# Powersupply.net
KiCad netlist of a schematic drawn in Altium Designer
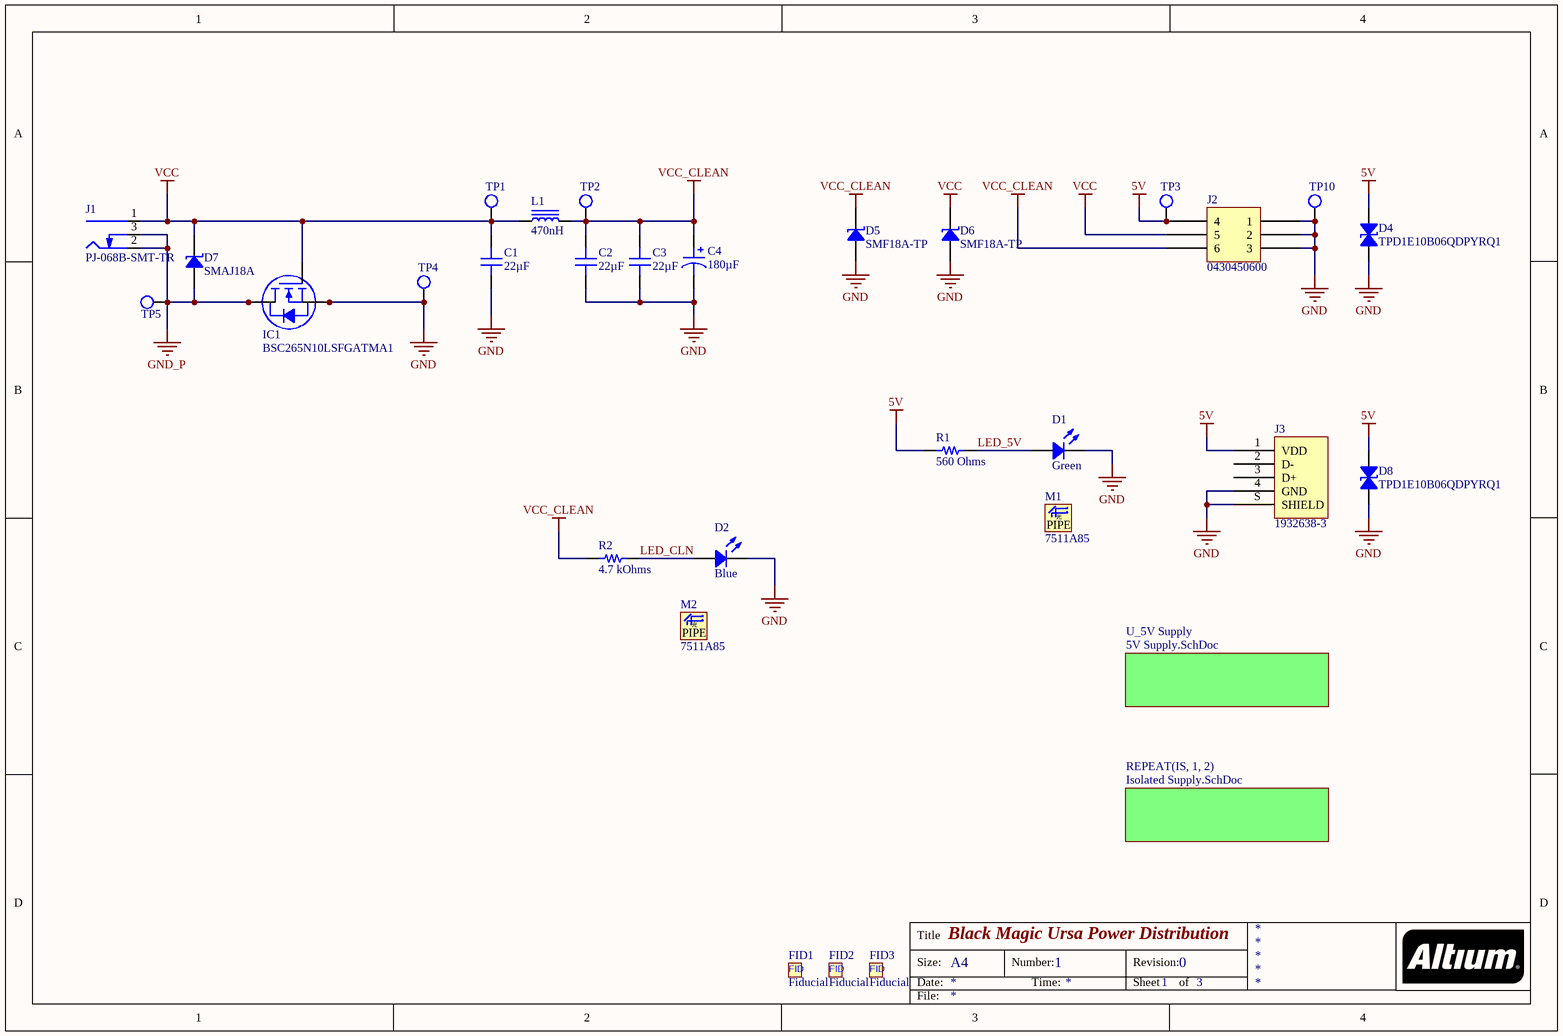
[diagram p0: Powersupply.SchDoc]

(export (version "E")
  (design (tool "Eeschema 10.0.6"))
  (components
    (comp (ref "C1")
      (value "22µF")
      (footprint "CAP 1210_3225 - 2.8MM")
      (description "CAP CER 22UF 25V X5R 1210")
      (fields
        (field (name "PART NUMBER") "CL32A226KAJNNNE")
        (field (name "MANUFACTURER") "Samsung Electro-Mechanics")
      )
      (libsource (lib "Celestial Altium Library - altium_library") (part "Capacitor"))
    )
    (comp (ref "C2")
      (value "22µF")
      (footprint "CAP 1210_3225 - 2.8MM")
      (description "CAP CER 22UF 25V X5R 1210")
      (fields
        (field (name "PART NUMBER") "CL32A226KAJNNNE")
        (field (name "MANUFACTURER") "Samsung Electro-Mechanics")
      )
      (libsource (lib "Celestial Altium Library - altium_library") (part "Capacitor"))
    )
    (comp (ref "C3")
      (value "22µF")
      (footprint "CAP 2220_5650 3.0MM")
      (description "CAP CER 22UF 25V X7R 2220")
      (fields
        (field (name "MANUFACTURER") "TDK Corporation")
        (field (name "PART NUMBER") "C5750X7R1E226M250KA")
      )
      (libsource (lib "Celestial Altium Library - altium_library") (part "Capacitor"))
    )
    (comp (ref "C4")
      (value "180µF")
      (footprint "CAP ALSMD POLY 8.3MM H7.0MM")
      (description "CAP ALUM POLY 180UF 20% 20V SMD")
      (fields
        (field (name "PART NUMBER") "APXG200ARA181MH70G")
        (field (name "MANUFACTURER") "United Chemi-Con")
      )
      (libsource (lib "Celestial Altium Library - altium_library") (part "Polarised Capacitor"))
    )
    (comp (ref "D1")
      (value "Green")
      (footprint "LED 0805_2012 GREEN")
      (description "LED GREEN CLEAR SMD")
      (fields (field (name "PART NUMBER") "LTST-C170GKT") (field (name "MANUFACTURER") "Lite-On Inc."))
      (libsource (lib "Celestial Altium Library - altium_library") (part "LED"))
    )
    (comp (ref "D2")
      (value "Blue")
      (footprint "LED 0805_2012 BLUE")
      (description "LED BLUE CLEAR 0805 SMD")
      (fields (field (name "PART NUMBER") "IN-S85AT5B") (field (name "MANUFACTURER") "Inolux"))
      (libsource (lib "Celestial Altium Library - altium_library") (part "LED"))
    )
    (comp (ref "D4")
      (value "TPD1E10B06QDPYRQ1")
      (footprint "0402")
      (description "TVS DIODE 5.5V 14V 2X1SON")
      (fields (field (name "MANUFACTURER") "Texas Instruments"))
      (libsource (lib "Celestial Altium Library - altium_library") (part "Diode TVS"))
    )
    (comp (ref "D5")
      (value "SMF18A-TP")
      (footprint "SOD123F")
      (description "TVS DIODE 18V 29.2V SOD123FL")
      (fields (field (name "MANUFACTURER") "Micro Commercial Co"))
      (libsource (lib "Celestial Altium Library - altium_library") (part "DIODE TVS UNI"))
    )
    (comp (ref "D6")
      (value "SMF18A-TP")
      (footprint "SOD123F")
      (description "TVS DIODE 18V 29.2V SOD123FL")
      (fields (field (name "MANUFACTURER") "Micro Commercial Co"))
      (libsource (lib "Celestial Altium Library - altium_library") (part "DIODE TVS UNI"))
    )
    (comp (ref "D7")
      (value "SMAJ18A")
      (footprint "DO214AC SMA")
      (description "TVS DIODE 18V 29.2V SMA")
      (fields (field (name "MANUFACTURER") "Bourns Inc."))
      (libsource (lib "Celestial Altium Library - altium_library") (part "DIODE TVS UNI"))
    )
    (comp (ref "D8")
      (value "TPD1E10B06QDPYRQ1")
      (footprint "0402")
      (description "TVS DIODE 5.5V 14V 2X1SON")
      (fields (field (name "MANUFACTURER") "Texas Instruments"))
      (libsource (lib "Celestial Altium Library - altium_library") (part "Diode TVS"))
    )
    (comp (ref "FID1")
      (value "Fiducial")
      (footprint "Fiducial-1mm")
      (libsource (lib "CelestialUseful") (part "Fiducial"))
    )
    (comp (ref "FID2")
      (value "Fiducial")
      (footprint "Fiducial-1mm")
      (libsource (lib "CelestialUseful") (part "Fiducial"))
    )
    (comp (ref "FID3")
      (value "Fiducial")
      (footprint "Fiducial-1mm")
      (libsource (lib "CelestialUseful") (part "Fiducial"))
    )
    (comp (ref "IC1")
      (value "BSC265N10LSFGATMA1")
      (footprint "INFINEON PG-TDSON-8 6.15X5.32MM")
      (description "MOSFET N-CH 100V 40A TDSON-8")
      (fields (field (name "MANUFACTURER") "Infineon Technologies"))
      (libsource (lib "Celestial Altium Library - altium_library") (part "INFINEON BSC MOSFET N-CH"))
    )
    (comp (ref "J1")
      (value "PJ-068B-SMT-TR")
      (footprint "CUI PJ-068B-SMT")
      (description "CONN PWR JACK 2.5X5.5MM SOLDER")
      (fields (field (name "MANUFACTURER") "CUI Devices"))
      (libsource (lib "Celestial Altium Library - altium_library") (part "Barrel Connector"))
    )
    (comp (ref "J2")
      (value "0430450600")
      (footprint "MOLEX MICRO-FIT 3.0 0430450600")
      (description "CONN HEADER R/A 6POS 3MM")
      (fields (field (name "MANUFACTURER") "Molex"))
      (libsource (lib "Celestial Altium Library - altium_library") (part "2x3 Pin"))
    )
    (comp (ref "J3")
      (value "1932638-3")
      (footprint "TE 1932638-3 USB2.0A")
      (description "CONN RCPT USB2.0 TYPEA 4P SMD RA")
      (fields (field (name "MANUFACTURER") "TE Connectivity AMP Connectors"))
      (libsource (lib "Celestial Altium Library - altium_library") (part "TE 1932638-3"))
    )
    (comp (ref "L1")
      (value "470nH")
      (footprint "WURTH WE-HCM H9.0MM")
      (description "FIXED IND 470NH 47.5A 0.165 MOHM")
      (fields (field (name "PART NUMBER") "744309047") (field (name "MANUFACTURER") "Würth Elektronik"))
      (libsource (lib "Celestial Altium Library - altium_library") (part "Inductor"))
    )
    (comp (ref "M1")
      (value "7511A85")
      (footprint "VCC 7511A85")
      (description "LIGHT PIPE RIGHT ANG SINGLE POS")
      (fields (field (name "MANUFACTURER") "Visual Communications Company - VCC"))
      (libsource (lib "Celestial Altium Library - altium_library") (part "Light Pipe"))
    )
    (comp (ref "M2")
      (value "7511A85")
      (footprint "VCC 7511A85")
      (description "LIGHT PIPE RIGHT ANG SINGLE POS")
      (fields (field (name "MANUFACTURER") "Visual Communications Company - VCC"))
      (libsource (lib "Celestial Altium Library - altium_library") (part "Light Pipe"))
    )
    (comp (ref "R1")
      (value "560 Ohms")
      (footprint "RES 0603_1608")
      (description "RES SMD 560 OHM 5% 1/4W 0603")
      (fields
        (field (name "PART NUMBER") "ERJ-PA3J561V")
        (field (name "MANUFACTURER") "Panasonic Electronic Components")
      )
      (libsource (lib "Celestial Altium Library - altium_library") (part "Resistor"))
    )
    (comp (ref "R2")
      (value "4.7 kOhms")
      (footprint "RES 0603_1608")
      (description "RES SMD 4.7K OHM 5% 1/4W 0603")
      (fields
        (field (name "PART NUMBER") "ERJ-PA3J472V")
        (field (name "MANUFACTURER") "Panasonic Electronic Components")
      )
      (libsource (lib "Celestial Altium Library - altium_library") (part "Resistor"))
    )
    (comp (ref "TP1")
      (value "Test Point")
      (footprint "TestPoint-1.5mm")
      (libsource (lib "CelestialUseful") (part "Test Point"))
    )
    (comp (ref "TP2")
      (value "Test Point")
      (footprint "TestPoint-1.5mm")
      (libsource (lib "CelestialUseful") (part "Test Point"))
    )
    (comp (ref "TP3")
      (value "Test Point")
      (footprint "TestPoint-1.5mm")
      (libsource (lib "CelestialUseful") (part "Test Point"))
    )
    (comp (ref "TP4")
      (value "Test Point")
      (footprint "TestPoint-1.5mm")
      (libsource (lib "CelestialUseful") (part "Test Point"))
    )
    (comp (ref "TP5")
      (value "Test Point")
      (footprint "TestPoint-1.5mm")
      (libsource (lib "CelestialUseful") (part "Test Point"))
    )
    (comp (ref "TP10")
      (value "Test Point")
      (footprint "TestPoint-1.5mm")
      (libsource (lib "CelestialUseful") (part "Test Point"))
    )
  )
  (nets
    (net (code "1") (name "/LED_5V") (class "Default")
      (node (ref "D1") (pin "1") (pinfunction "1_1") (pintype "passive"))
      (node (ref "R1") (pin "2") (pinfunction "2_2") (pintype "passive"))
    )
    (net (code "2") (name "/LED_CLN") (class "Default")
      (node (ref "D2") (pin "1") (pinfunction "1_1") (pintype "passive"))
      (node (ref "R2") (pin "2") (pinfunction "2_2") (pintype "passive"))
    )
    (net (code "3") (name "5V") (class "Default")
      (node (ref "D4") (pin "2") (pinfunction "2_2") (pintype "passive"))
      (node (ref "D8") (pin "2") (pinfunction "2_2") (pintype "passive"))
      (node (ref "J2") (pin "4") (pinfunction "4_4") (pintype "passive"))
      (node (ref "J3") (pin "1") (pinfunction "VDD_1") (pintype "passive"))
      (node (ref "R1") (pin "1") (pinfunction "1_1") (pintype "passive"))
      (node (ref "TP3") (pin "1") (pinfunction "TP_1") (pintype "passive"))
    )
    (net (code "4") (name "GND") (class "Default")
      (node (ref "C1") (pin "1") (pinfunction "1_1") (pintype "passive"))
      (node (ref "C2") (pin "1") (pinfunction "1_1") (pintype "passive"))
      (node (ref "C3") (pin "1") (pinfunction "1_1") (pintype "passive"))
      (node (ref "C4") (pin "2") (pinfunction "2_2") (pintype "passive"))
      (node (ref "D1") (pin "2") (pinfunction "2_2") (pintype "passive"))
      (node (ref "D2") (pin "2") (pinfunction "2_2") (pintype "passive"))
      (node (ref "D4") (pin "1") (pinfunction "1_1") (pintype "passive"))
      (node (ref "D5") (pin "1") (pinfunction "1_1") (pintype "passive"))
      (node (ref "D6") (pin "1") (pinfunction "1_1") (pintype "passive"))
      (node (ref "D8") (pin "1") (pinfunction "1_1") (pintype "passive"))
      (node (ref "IC1") (pin "1") (pinfunction "S_1") (pintype "passive"))
      (node (ref "IC1") (pin "2") (pinfunction "S_2") (pintype "passive"))
      (node (ref "IC1") (pin "3") (pinfunction "S_3") (pintype "passive"))
      (node (ref "J2") (pin "1") (pinfunction "1_1") (pintype "passive"))
      (node (ref "J2") (pin "2") (pinfunction "2_2") (pintype "passive"))
      (node (ref "J2") (pin "3") (pinfunction "3_3") (pintype "passive"))
      (node (ref "J3") (pin "4") (pinfunction "GND_4") (pintype "passive"))
      (node (ref "J3") (pin "S") (pinfunction "SHIELD_S") (pintype "passive"))
      (node (ref "TP10") (pin "1") (pinfunction "TP_1") (pintype "passive"))
      (node (ref "TP4") (pin "1") (pinfunction "TP_1") (pintype "passive"))
    )
    (net (code "5") (name "GND_P") (class "Default")
      (node (ref "D7") (pin "1") (pinfunction "1_1") (pintype "passive"))
      (node (ref "IC1") (pin "5") (pinfunction "D_5") (pintype "passive"))
      (node (ref "IC1") (pin "6") (pinfunction "D_6") (pintype "passive"))
      (node (ref "IC1") (pin "7") (pinfunction "D_7") (pintype "passive"))
      (node (ref "IC1") (pin "8") (pinfunction "D_8") (pintype "passive"))
      (node (ref "J1") (pin "2") (pinfunction "Outer_2") (pintype "passive"))
      (node (ref "J1") (pin "3") (pinfunction "SW_3") (pintype "passive"))
      (node (ref "TP5") (pin "1") (pinfunction "TP_1") (pintype "passive"))
    )
    (net (code "6") (name "VCC") (class "Default")
      (node (ref "C1") (pin "2") (pinfunction "2_2") (pintype "passive"))
      (node (ref "D6") (pin "2") (pinfunction "2_2") (pintype "passive"))
      (node (ref "D7") (pin "2") (pinfunction "2_2") (pintype "passive"))
      (node (ref "IC1") (pin "4") (pinfunction "G_4") (pintype "passive"))
      (node (ref "J1") (pin "1") (pinfunction "Centre_1") (pintype "passive"))
      (node (ref "J2") (pin "5") (pinfunction "5_5") (pintype "passive"))
      (node (ref "L1") (pin "1") (pinfunction "1_1") (pintype "passive"))
      (node (ref "TP1") (pin "1") (pinfunction "TP_1") (pintype "passive"))
    )
    (net (code "7") (name "VCC_CLEAN") (class "Default")
      (node (ref "C2") (pin "2") (pinfunction "2_2") (pintype "passive"))
      (node (ref "C3") (pin "2") (pinfunction "2_2") (pintype "passive"))
      (node (ref "C4") (pin "1") (pinfunction "1_1") (pintype "passive"))
      (node (ref "D5") (pin "2") (pinfunction "2_2") (pintype "passive"))
      (node (ref "J2") (pin "6") (pinfunction "6_6") (pintype "passive"))
      (node (ref "L1") (pin "2") (pinfunction "2_2") (pintype "passive"))
      (node (ref "R2") (pin "1") (pinfunction "1_1") (pintype "passive"))
      (node (ref "TP2") (pin "1") (pinfunction "TP_1") (pintype "passive"))
    )
    (net (code "8") (name "unconnected-(J3-D+-Pad3)") (class "Default")
      (node (ref "J3") (pin "3") (pinfunction "D+_3") (pintype "passive"))
    )
    (net (code "9") (name "unconnected-(J3-D--Pad2)") (class "Default")
      (node (ref "J3") (pin "2") (pinfunction "D-_2") (pintype "passive"))
    )
  )
)
